# TB6612-4.net
KiCad netlist of a schematic drawn in EasyEDA Pro
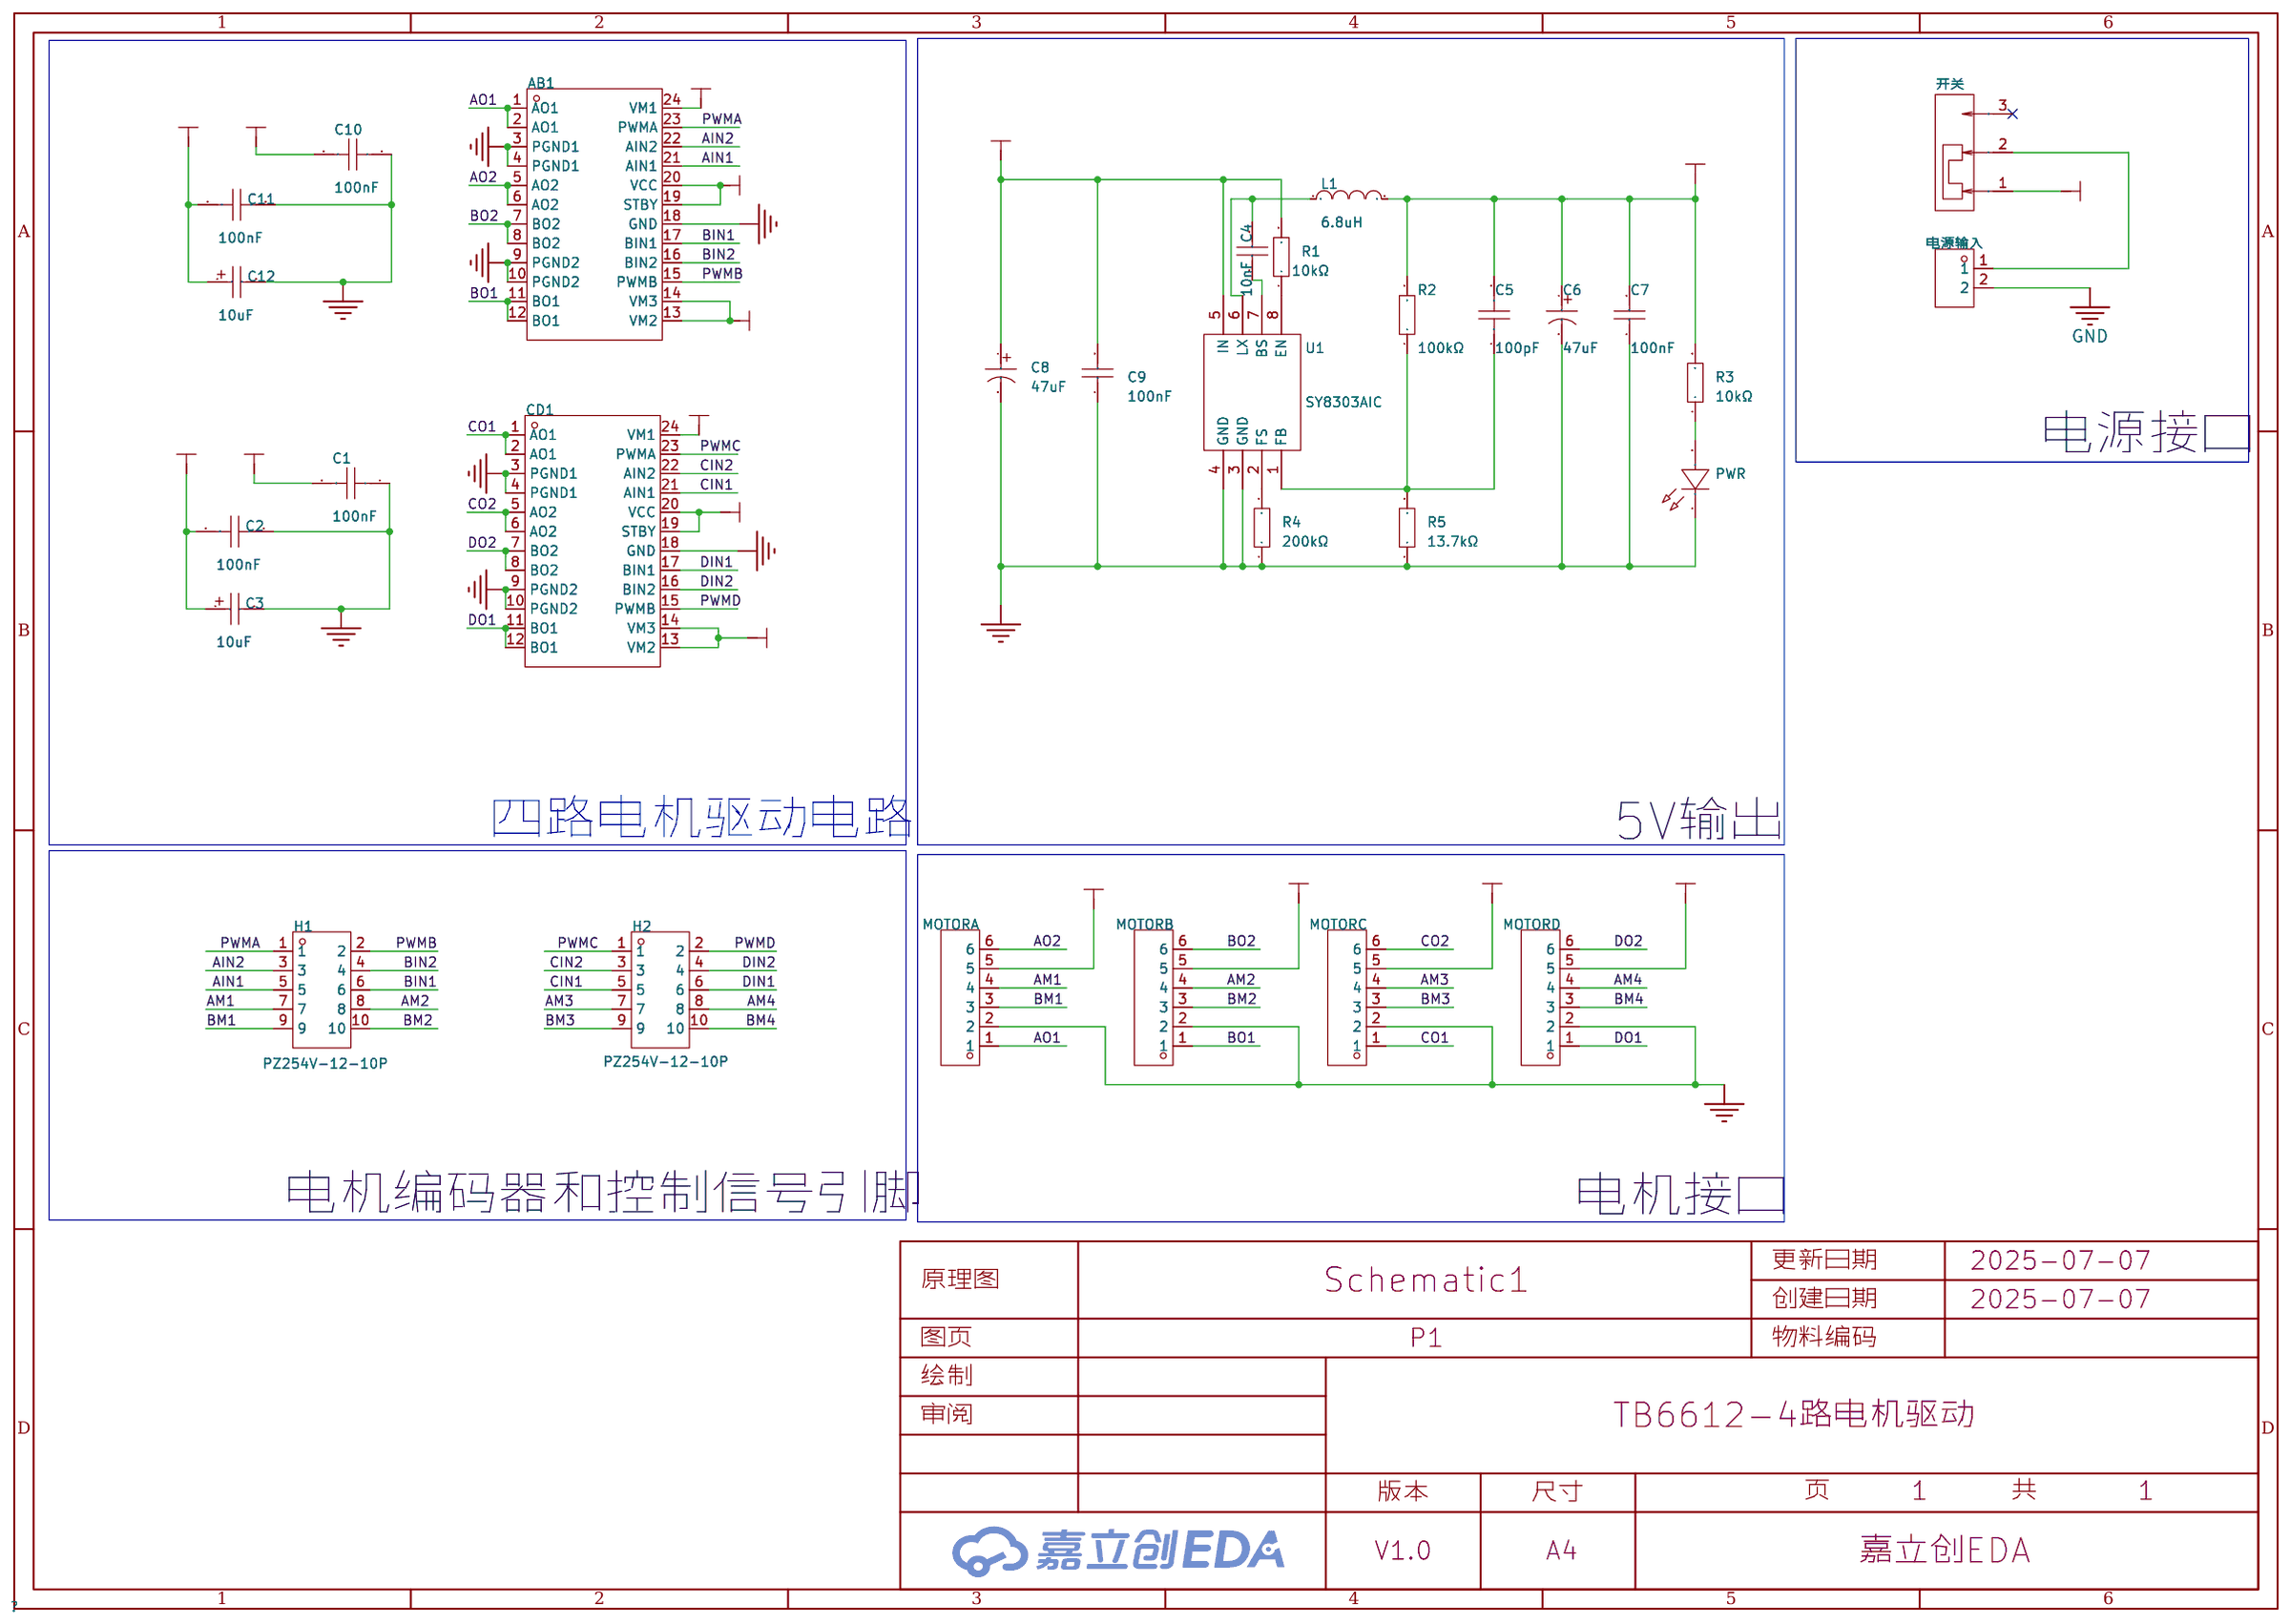
[diagram p0: schematic sheet]

(export (version "E")
  (design (tool "Eeschema 10.0.6"))
  (components
    (comp (ref "AB1")
      (value "TB6612FNG(O,C,8,EL")
      (footprint "easyedapro:SSOP-24_L8.4-W5.8-P0.65-LS7.8-BL")
      (description "双直流电机驱动器集成电路")
      (fields (field (name "Manufacturer") "TOSHIBA(东芝)"))
      (libsource (lib "easyedapro") (part "TB6612FNG(O,C,8,EL"))
    )
    (comp (ref "C1")
      (value "100nF")
      (footprint "easyedapro:C0603")
      (description "容值:100nF;精度:±10%;额定电压:50V;材质(温度系数):X7R;")
      (fields
        (field (name "Manufacturer Part") "CL10B104KB8NNNC")
        (field (name "Manufacturer") "SAMSUNG(三星)")
      )
      (libsource (lib "easyedapro") (part "CL10B104KB8NNNC"))
    )
    (comp (ref "C2")
      (value "100nF")
      (footprint "easyedapro:C0603")
      (description "容值:100nF;精度:±10%;额定电压:50V;材质(温度系数):X7R;")
      (fields
        (field (name "Manufacturer Part") "CL10B104KB8NNNC")
        (field (name "Manufacturer") "SAMSUNG(三星)")
      )
      (libsource (lib "easyedapro") (part "CL10B104KB8NNNC"))
    )
    (comp (ref "C3")
      (value "10uF")
      (footprint "easyedapro:CAP-SMD_L3.5-W2.8-R-RD")
      (description "容值:10uF;精度:±10%;额定电压:25V;等效串联电阻:2.5Ω@100kHz;")
      (fields (field (name "Manufacturer Part") "TAJB106K025RNJ") (field (name "Manufacturer") "Kyocera AVX"))
      (libsource (lib "easyedapro") (part "TAJB106K025RNJ"))
    )
    (comp (ref "C4")
      (value "10nF")
      (footprint "easyedapro:C0603")
      (description "容值:10nF;精度:±10%;额定电压:50V;材质(温度系数):X7R;")
      (fields
        (field (name "Manufacturer Part") "CC0603KRX7R9BB103")
        (field (name "Manufacturer") "YAGEO(国巨)")
      )
      (libsource (lib "easyedapro") (part "CC0603KRX7R9BB103"))
    )
    (comp (ref "C5")
      (value "100pF")
      (footprint "easyedapro:C0603")
      (description "容值:100pF;精度:±5%;额定电压:50V;材质(温度系数):NP0;")
      (fields
        (field (name "Manufacturer Part") "CC0603JRNPO9BN101")
        (field (name "Manufacturer") "YAGEO(国巨)")
      )
      (libsource (lib "easyedapro") (part "CC0603JRNPO9BN101"))
    )
    (comp (ref "C6")
      (value "47uF")
      (footprint "easyedapro:CAP-SMD_BD6.3-L6.6-W6.6-LS7.6-FD")
      (description "容值:47uF;精度:±20%;额定电压:50V;纹波电流:66mA@120Hz;等效串联电阻:-;")
      (fields (field (name "Manufacturer Part") "RVT1H470M0607") (field (name "Manufacturer") "ROQANG(容强)"))
      (libsource (lib "easyedapro") (part "RVT1H470M0607"))
    )
    (comp (ref "C7")
      (value "100nF")
      (footprint "easyedapro:C0603")
      (description "容值:100nF;精度:±10%;额定电压:50V;材质(温度系数):X7R;")
      (fields (field (name "Manufacturer Part") "0603B104K500NT") (field (name "Manufacturer") "FH(风华)"))
      (libsource (lib "easyedapro") (part "0603B104K500NT"))
    )
    (comp (ref "C8")
      (value "47uF")
      (footprint "easyedapro:CAP-SMD_BD6.3-L6.6-W6.6-LS7.6-FD")
      (description "容值:47uF;精度:±20%;额定电压:50V;纹波电流:66mA@120Hz;等效串联电阻:-;")
      (fields (field (name "Manufacturer Part") "RVT1H470M0607") (field (name "Manufacturer") "ROQANG(容强)"))
      (libsource (lib "easyedapro") (part "RVT1H470M0607"))
    )
    (comp (ref "C9")
      (value "100nF")
      (footprint "easyedapro:C0603")
      (description "容值:100nF;精度:±10%;额定电压:50V;材质(温度系数):X7R;")
      (fields (field (name "Manufacturer Part") "0603B104K500NT") (field (name "Manufacturer") "FH(风华)"))
      (libsource (lib "easyedapro") (part "0603B104K500NT"))
    )
    (comp (ref "C10")
      (value "100nF")
      (footprint "easyedapro:C0603")
      (description "容值:100nF;精度:±10%;额定电压:50V;材质(温度系数):X7R;")
      (fields
        (field (name "Manufacturer Part") "CL10B104KB8NNNC")
        (field (name "Manufacturer") "SAMSUNG(三星)")
      )
      (libsource (lib "easyedapro") (part "CL10B104KB8NNNC"))
    )
    (comp (ref "C11")
      (value "100nF")
      (footprint "easyedapro:C0603")
      (description "容值:100nF;精度:±10%;额定电压:50V;材质(温度系数):X7R;")
      (fields
        (field (name "Manufacturer Part") "CL10B104KB8NNNC")
        (field (name "Manufacturer") "SAMSUNG(三星)")
      )
      (libsource (lib "easyedapro") (part "CL10B104KB8NNNC"))
    )
    (comp (ref "C12")
      (value "10uF")
      (footprint "easyedapro:CAP-SMD_L3.5-W2.8-R-RD")
      (description "容值:10uF;精度:±10%;额定电压:25V;等效串联电阻:2.5Ω@100kHz;")
      (fields (field (name "Manufacturer Part") "TAJB106K025RNJ") (field (name "Manufacturer") "Kyocera AVX"))
      (libsource (lib "easyedapro") (part "TAJB106K025RNJ"))
    )
    (comp (ref "CD1")
      (value "TB6612FNG(O,C,8,EL")
      (footprint "easyedapro:SSOP-24_L8.4-W5.8-P0.65-LS7.8-BL")
      (description "双直流电机驱动器集成电路")
      (fields (field (name "Manufacturer") "TOSHIBA(东芝)"))
      (libsource (lib "easyedapro") (part "TB6612FNG(O,C,8,EL"))
    )
    (comp (ref "H1")
      (value "PZ254V-12-10P")
      (footprint "easyedapro:HDR-TH_10P-P2.54-V-M-R2-C5-S2.54")
      (fields (field (name "Manufacturer") "XFCN(兴飞)"))
      (libsource (lib "easyedapro") (part "PZ254V-12-10P"))
    )
    (comp (ref "H2")
      (value "PZ254V-12-10P")
      (footprint "easyedapro:HDR-TH_10P-P2.54-V-M-R2-C5-S2.54")
      (fields (field (name "Manufacturer") "XFCN(兴飞)"))
      (libsource (lib "easyedapro") (part "PZ254V-12-10P"))
    )
    (comp (ref "L1")
      (value "6.8uH")
      (footprint "easyedapro:IND-SMD_L4.4-W4.2")
      (description "电感值:6.8uH;精度:±20%;额定电流:2.4A;饱和电流(Isat):2.5A;类型:一体成型电感;")
      (fields (field (name "Manufacturer Part") "FXL0420-6R8-M") (field (name "Manufacturer") "cjiang(长江微电)"))
      (libsource (lib "easyedapro") (part "FXL0420-6R8-M"))
    )
    (comp (ref "MOTORA")
      (value "X8821WR-06S-N0SN")
      (footprint "easyedapro:CONN-TH_6P-P2.50_X8821WR-06S-N2SN")
      (description "插针结构:1x6P;间距:2.5mm;安装方式:弯插;参考系列:XH;总PIN数:6P;排数:1;每排PIN数:6;行距:-;额定电流:3A;触头材质:黄铜;触头镀层:锡;工作温度范围:-;")
      (fields (field (name "Manufacturer") "XKB Connection(中国星坤)"))
      (libsource (lib "easyedapro") (part "X8821WR-06S-N0SN"))
    )
    (comp (ref "MOTORB")
      (value "X8821WR-06S-N0SN")
      (footprint "easyedapro:CONN-TH_6P-P2.50_X8821WR-06S-N2SN")
      (description "插针结构:1x6P;间距:2.5mm;安装方式:弯插;参考系列:XH;总PIN数:6P;排数:1;每排PIN数:6;行距:-;额定电流:3A;触头材质:黄铜;触头镀层:锡;工作温度范围:-;")
      (fields (field (name "Manufacturer") "XKB Connection(中国星坤)"))
      (libsource (lib "easyedapro") (part "X8821WR-06S-N0SN"))
    )
    (comp (ref "MOTORC")
      (value "X8821WR-06S-N0SN")
      (footprint "easyedapro:CONN-TH_6P-P2.50_X8821WR-06S-N2SN")
      (description "插针结构:1x6P;间距:2.5mm;安装方式:弯插;参考系列:XH;总PIN数:6P;排数:1;每排PIN数:6;行距:-;额定电流:3A;触头材质:黄铜;触头镀层:锡;工作温度范围:-;")
      (fields (field (name "Manufacturer") "XKB Connection(中国星坤)"))
      (libsource (lib "easyedapro") (part "X8821WR-06S-N0SN"))
    )
    (comp (ref "MOTORD")
      (value "X8821WR-06S-N0SN")
      (footprint "easyedapro:CONN-TH_6P-P2.50_X8821WR-06S-N2SN")
      (description "插针结构:1x6P;间距:2.5mm;安装方式:弯插;参考系列:XH;总PIN数:6P;排数:1;每排PIN数:6;行距:-;额定电流:3A;触头材质:黄铜;触头镀层:锡;工作温度范围:-;")
      (fields (field (name "Manufacturer") "XKB Connection(中国星坤)"))
      (libsource (lib "easyedapro") (part "X8821WR-06S-N0SN"))
    )
    (comp (ref "PWR")
      (value "XL-1608UGC-04")
      (footprint "easyedapro:LED0603-RD_GREEN")
      (fields (field (name "Manufacturer") "XINGLIGHT(成兴光)"))
      (libsource (lib "easyedapro") (part "XL-1608UGC-04"))
    )
    (comp (ref "R1")
      (value "10kΩ")
      (footprint "easyedapro:R0603")
      (description "电阻类型:厚膜电阻;阻值:10kΩ;精度:±1%;功率:100mW;最大工作电压:75V;温度系数:±100ppm/°C;")
      (fields
        (field (name "Manufacturer Part") "0603WAF1002T5E")
        (field (name "Manufacturer") "UNI-ROYAL(厚声)")
      )
      (libsource (lib "easyedapro") (part "0603WAF1002T5E"))
    )
    (comp (ref "R2")
      (value "100kΩ")
      (footprint "easyedapro:R0603")
      (description "电阻类型:厚膜电阻;阻值:100kΩ;精度:±1%;功率:100mW;最大工作电压:75V;温度系数:±100ppm/°C;")
      (fields
        (field (name "Manufacturer Part") "0603WAF1003T5E")
        (field (name "Manufacturer") "UNI-ROYAL(厚声)")
      )
      (libsource (lib "easyedapro") (part "0603WAF1003T5E"))
    )
    (comp (ref "R3")
      (value "10kΩ")
      (footprint "easyedapro:R0603")
      (description "电阻类型:厚膜电阻;阻值:10kΩ;精度:±1%;功率:100mW;最大工作电压:75V;温度系数:±100ppm/°C;")
      (fields
        (field (name "Manufacturer Part") "0603WAF1002T5E")
        (field (name "Manufacturer") "UNI-ROYAL(厚声)")
      )
      (libsource (lib "easyedapro") (part "0603WAF1002T5E"))
    )
    (comp (ref "R4")
      (value "200kΩ")
      (footprint "easyedapro:R0603")
      (description "电阻类型:厚膜电阻;阻值:200kΩ;精度:±1%;功率:100mW;最大工作电压:75V;温度系数:±100ppm/°C;")
      (fields
        (field (name "Manufacturer Part") "0603WAF2003T5E")
        (field (name "Manufacturer") "UNI-ROYAL(厚声)")
      )
      (libsource (lib "easyedapro") (part "0603WAF2003T5E"))
    )
    (comp (ref "R5")
      (value "13.7kΩ")
      (footprint "easyedapro:R0603")
      (description "电阻类型:厚膜电阻;阻值:13.7kΩ;精度:±1%;功率:100mW;最大工作电压:75V;温度系数:±100ppm/°C;")
      (fields
        (field (name "Manufacturer Part") "0603WAF1372T5E")
        (field (name "Manufacturer") "UNI-ROYAL(厚声)")
      )
      (libsource (lib "easyedapro") (part "0603WAF1372T5E"))
    )
    (comp (ref "U1")
      (value "SY8303AIC")
      (footprint "easyedapro:TSOT-23-8_L2.9-W1.6-P0.65-LS2.8-BR")
      (description "功能类型:降压型;输入电压:-;输出电流(最大值):-;")
      (fields (field (name "Manufacturer") "silergy(矽力杰)"))
      (libsource (lib "easyedapro") (part "SY8303AIC"))
    )
    (comp (ref "开关")
      (value "SS-12D10-G5")
      (footprint "easyedapro:SW-TH_SS-12D10-G050")
      (description "电路结构:单刀双掷;安装方式:直插;开关颜色:黑色;滑钮形状:矩形柱状;引脚样式:PC引脚;开关长度:12.7mm;开关宽度:6.7mm;开关高度:11.3mm;")
      (fields (field (name "Manufacturer") "DEALON(德艺隆)"))
      (libsource (lib "easyedapro") (part "SS-12D10-G5"))
    )
    (comp (ref "电源输入")
      (value "KF301-5.0-2P")
      (footprint "easyedapro:CONN-TH_P5.00_KF301-5.0-2P")
      (fields (field (name "Manufacturer") "KEFA(科发)"))
      (libsource (lib "easyedapro") (part "KF301-5.0-2P"))
    )
  )
  (nets
    (net (code "1") (name "/AIN1") (class "Default")
      (node (ref "AB1") (pin "21") (pinfunction "AIN1_21") (pintype "unspecified"))
      (node (ref "H1") (pin "5") (pinfunction "5_5") (pintype "unspecified"))
    )
    (net (code "2") (name "/AIN2") (class "Default")
      (node (ref "AB1") (pin "22") (pinfunction "AIN2_22") (pintype "unspecified"))
      (node (ref "H1") (pin "3") (pinfunction "3_3") (pintype "unspecified"))
    )
    (net (code "3") (name "/AM1") (class "Default")
      (node (ref "H1") (pin "7") (pinfunction "7_7") (pintype "unspecified"))
      (node (ref "MOTORA") (pin "4") (pinfunction "4_4") (pintype "unspecified"))
    )
    (net (code "4") (name "/AM2") (class "Default")
      (node (ref "H1") (pin "8") (pinfunction "8_8") (pintype "unspecified"))
      (node (ref "MOTORB") (pin "4") (pinfunction "4_4") (pintype "unspecified"))
    )
    (net (code "5") (name "/AM3") (class "Default")
      (node (ref "H2") (pin "7") (pinfunction "7_7") (pintype "unspecified"))
      (node (ref "MOTORC") (pin "4") (pinfunction "4_4") (pintype "unspecified"))
    )
    (net (code "6") (name "/AM4") (class "Default")
      (node (ref "H2") (pin "8") (pinfunction "8_8") (pintype "unspecified"))
      (node (ref "MOTORD") (pin "4") (pinfunction "4_4") (pintype "unspecified"))
    )
    (net (code "7") (name "/AO1") (class "Default")
      (node (ref "AB1") (pin "1") (pinfunction "AO1_1") (pintype "unspecified"))
      (node (ref "AB1") (pin "2") (pinfunction "AO1_2") (pintype "unspecified"))
      (node (ref "MOTORA") (pin "1") (pinfunction "1_1") (pintype "unspecified"))
    )
    (net (code "8") (name "/AO2") (class "Default")
      (node (ref "AB1") (pin "5") (pinfunction "AO2_5") (pintype "unspecified"))
      (node (ref "AB1") (pin "6") (pinfunction "AO2_6") (pintype "unspecified"))
      (node (ref "MOTORA") (pin "6") (pinfunction "6_6") (pintype "unspecified"))
    )
    (net (code "9") (name "/BIN1") (class "Default")
      (node (ref "AB1") (pin "17") (pinfunction "BIN1_17") (pintype "unspecified"))
      (node (ref "H1") (pin "6") (pinfunction "6_6") (pintype "unspecified"))
    )
    (net (code "10") (name "/BIN2") (class "Default")
      (node (ref "AB1") (pin "16") (pinfunction "BIN2_16") (pintype "unspecified"))
      (node (ref "H1") (pin "4") (pinfunction "4_4") (pintype "unspecified"))
    )
    (net (code "11") (name "/BM1") (class "Default")
      (node (ref "H1") (pin "9") (pinfunction "9_9") (pintype "unspecified"))
      (node (ref "MOTORA") (pin "3") (pinfunction "3_3") (pintype "unspecified"))
    )
    (net (code "12") (name "/BM2") (class "Default")
      (node (ref "H1") (pin "10") (pinfunction "10_10") (pintype "unspecified"))
      (node (ref "MOTORB") (pin "3") (pinfunction "3_3") (pintype "unspecified"))
    )
    (net (code "13") (name "/BM3") (class "Default")
      (node (ref "H2") (pin "9") (pinfunction "9_9") (pintype "unspecified"))
      (node (ref "MOTORC") (pin "3") (pinfunction "3_3") (pintype "unspecified"))
    )
    (net (code "14") (name "/BM4") (class "Default")
      (node (ref "H2") (pin "10") (pinfunction "10_10") (pintype "unspecified"))
      (node (ref "MOTORD") (pin "3") (pinfunction "3_3") (pintype "unspecified"))
    )
    (net (code "15") (name "/BO1") (class "Default")
      (node (ref "AB1") (pin "11") (pinfunction "BO1_11") (pintype "unspecified"))
      (node (ref "AB1") (pin "12") (pinfunction "BO1_12") (pintype "unspecified"))
      (node (ref "MOTORB") (pin "1") (pinfunction "1_1") (pintype "unspecified"))
    )
    (net (code "16") (name "/BO2") (class "Default")
      (node (ref "AB1") (pin "7") (pinfunction "BO2_7") (pintype "unspecified"))
      (node (ref "AB1") (pin "8") (pinfunction "BO2_8") (pintype "unspecified"))
      (node (ref "MOTORB") (pin "6") (pinfunction "6_6") (pintype "unspecified"))
    )
    (net (code "17") (name "/CIN1") (class "Default")
      (node (ref "CD1") (pin "21") (pinfunction "AIN1_21") (pintype "unspecified"))
      (node (ref "H2") (pin "5") (pinfunction "5_5") (pintype "unspecified"))
    )
    (net (code "18") (name "/CIN2") (class "Default")
      (node (ref "CD1") (pin "22") (pinfunction "AIN2_22") (pintype "unspecified"))
      (node (ref "H2") (pin "3") (pinfunction "3_3") (pintype "unspecified"))
    )
    (net (code "19") (name "/CO1") (class "Default")
      (node (ref "CD1") (pin "1") (pinfunction "AO1_1") (pintype "unspecified"))
      (node (ref "CD1") (pin "2") (pinfunction "AO1_2") (pintype "unspecified"))
      (node (ref "MOTORC") (pin "1") (pinfunction "1_1") (pintype "unspecified"))
    )
    (net (code "20") (name "/CO2") (class "Default")
      (node (ref "CD1") (pin "5") (pinfunction "AO2_5") (pintype "unspecified"))
      (node (ref "CD1") (pin "6") (pinfunction "AO2_6") (pintype "unspecified"))
      (node (ref "MOTORC") (pin "6") (pinfunction "6_6") (pintype "unspecified"))
    )
    (net (code "21") (name "/DIN1") (class "Default")
      (node (ref "CD1") (pin "17") (pinfunction "BIN1_17") (pintype "unspecified"))
      (node (ref "H2") (pin "6") (pinfunction "6_6") (pintype "unspecified"))
    )
    (net (code "22") (name "/DIN2") (class "Default")
      (node (ref "CD1") (pin "16") (pinfunction "BIN2_16") (pintype "unspecified"))
      (node (ref "H2") (pin "4") (pinfunction "4_4") (pintype "unspecified"))
    )
    (net (code "23") (name "/DO1") (class "Default")
      (node (ref "CD1") (pin "11") (pinfunction "BO1_11") (pintype "unspecified"))
      (node (ref "CD1") (pin "12") (pinfunction "BO1_12") (pintype "unspecified"))
      (node (ref "MOTORD") (pin "1") (pinfunction "1_1") (pintype "unspecified"))
    )
    (net (code "24") (name "/DO2") (class "Default")
      (node (ref "CD1") (pin "7") (pinfunction "BO2_7") (pintype "unspecified"))
      (node (ref "CD1") (pin "8") (pinfunction "BO2_8") (pintype "unspecified"))
      (node (ref "MOTORD") (pin "6") (pinfunction "6_6") (pintype "unspecified"))
    )
    (net (code "25") (name "/PWMA") (class "Default")
      (node (ref "AB1") (pin "23") (pinfunction "PWMA_23") (pintype "unspecified"))
      (node (ref "H1") (pin "1") (pinfunction "1_1") (pintype "unspecified"))
    )
    (net (code "26") (name "/PWMB") (class "Default")
      (node (ref "AB1") (pin "15") (pinfunction "PWMB_15") (pintype "unspecified"))
      (node (ref "H1") (pin "2") (pinfunction "2_2") (pintype "unspecified"))
    )
    (net (code "27") (name "/PWMC") (class "Default")
      (node (ref "CD1") (pin "23") (pinfunction "PWMA_23") (pintype "unspecified"))
      (node (ref "H2") (pin "1") (pinfunction "1_1") (pintype "unspecified"))
    )
    (net (code "28") (name "/PWMD") (class "Default")
      (node (ref "CD1") (pin "15") (pinfunction "PWMB_15") (pintype "unspecified"))
      (node (ref "H2") (pin "2") (pinfunction "2_2") (pintype "unspecified"))
    )
    (net (code "29") (name "5V") (class "Default")
      (node (ref "AB1") (pin "19") (pinfunction "STBY_19") (pintype "unspecified"))
      (node (ref "AB1") (pin "20") (pinfunction "VCC_20") (pintype "unspecified"))
      (node (ref "C1") (pin "2") (pinfunction "2_2") (pintype "unspecified"))
      (node (ref "C10") (pin "2") (pinfunction "2_2") (pintype "unspecified"))
      (node (ref "C5") (pin "2") (pinfunction "2_2") (pintype "unspecified"))
      (node (ref "C6") (pin "1") (pinfunction "1_1") (pintype "input"))
      (node (ref "C7") (pin "2") (pinfunction "2_2") (pintype "input"))
      (node (ref "CD1") (pin "19") (pinfunction "STBY_19") (pintype "unspecified"))
      (node (ref "CD1") (pin "20") (pinfunction "VCC_20") (pintype "unspecified"))
      (node (ref "L1") (pin "2") (pinfunction "2_2") (pintype "unspecified"))
      (node (ref "MOTORA") (pin "5") (pinfunction "5_5") (pintype "unspecified"))
      (node (ref "MOTORB") (pin "5") (pinfunction "5_5") (pintype "unspecified"))
      (node (ref "MOTORC") (pin "5") (pinfunction "5_5") (pintype "unspecified"))
      (node (ref "MOTORD") (pin "5") (pinfunction "5_5") (pintype "unspecified"))
      (node (ref "R2") (pin "2") (pinfunction "2_2") (pintype "input"))
      (node (ref "R3") (pin "2") (pinfunction "2_2") (pintype "input"))
    )
    (net (code "30") (name "12V") (class "Default")
      (node (ref "AB1") (pin "13") (pinfunction "VM2_13") (pintype "unspecified"))
      (node (ref "AB1") (pin "14") (pinfunction "VM3_14") (pintype "unspecified"))
      (node (ref "AB1") (pin "24") (pinfunction "VM1_24") (pintype "unspecified"))
      (node (ref "C11") (pin "2") (pinfunction "2_2") (pintype "unspecified"))
      (node (ref "C12") (pin "1") (pinfunction "1_1") (pintype "input"))
      (node (ref "C2") (pin "2") (pinfunction "2_2") (pintype "unspecified"))
      (node (ref "C3") (pin "1") (pinfunction "1_1") (pintype "input"))
      (node (ref "C8") (pin "1") (pinfunction "1_1") (pintype "input"))
      (node (ref "C9") (pin "2") (pinfunction "2_2") (pintype "input"))
      (node (ref "CD1") (pin "13") (pinfunction "VM2_13") (pintype "unspecified"))
      (node (ref "CD1") (pin "14") (pinfunction "VM3_14") (pintype "unspecified"))
      (node (ref "CD1") (pin "24") (pinfunction "VM1_24") (pintype "unspecified"))
      (node (ref "R1") (pin "2") (pinfunction "2_2") (pintype "input"))
      (node (ref "U1") (pin "5") (pinfunction "IN_5") (pintype "input"))
      (node (ref "开关") (pin "1") (pinfunction "1_1") (pintype "input"))
    )
    (net (code "31") (name "GND") (class "Default")
      (node (ref "AB1") (pin "10") (pinfunction "PGND2_10") (pintype "unspecified"))
      (node (ref "AB1") (pin "18") (pinfunction "GND_18") (pintype "unspecified"))
      (node (ref "AB1") (pin "3") (pinfunction "PGND1_3") (pintype "unspecified"))
      (node (ref "AB1") (pin "4") (pinfunction "PGND1_4") (pintype "unspecified"))
      (node (ref "AB1") (pin "9") (pinfunction "PGND2_9") (pintype "unspecified"))
      (node (ref "C1") (pin "1") (pinfunction "1_1") (pintype "unspecified"))
      (node (ref "C10") (pin "1") (pinfunction "1_1") (pintype "unspecified"))
      (node (ref "C11") (pin "1") (pinfunction "1_1") (pintype "unspecified"))
      (node (ref "C12") (pin "2") (pinfunction "2_2") (pintype "input"))
      (node (ref "C2") (pin "1") (pinfunction "1_1") (pintype "unspecified"))
      (node (ref "C3") (pin "2") (pinfunction "2_2") (pintype "input"))
      (node (ref "C6") (pin "2") (pinfunction "2_2") (pintype "input"))
      (node (ref "C7") (pin "1") (pinfunction "1_1") (pintype "input"))
      (node (ref "C8") (pin "2") (pinfunction "2_2") (pintype "input"))
      (node (ref "C9") (pin "1") (pinfunction "1_1") (pintype "input"))
      (node (ref "CD1") (pin "10") (pinfunction "PGND2_10") (pintype "unspecified"))
      (node (ref "CD1") (pin "18") (pinfunction "GND_18") (pintype "unspecified"))
      (node (ref "CD1") (pin "3") (pinfunction "PGND1_3") (pintype "unspecified"))
      (node (ref "CD1") (pin "4") (pinfunction "PGND1_4") (pintype "unspecified"))
      (node (ref "CD1") (pin "9") (pinfunction "PGND2_9") (pintype "unspecified"))
      (node (ref "MOTORA") (pin "2") (pinfunction "2_2") (pintype "unspecified"))
      (node (ref "MOTORB") (pin "2") (pinfunction "2_2") (pintype "unspecified"))
      (node (ref "MOTORC") (pin "2") (pinfunction "2_2") (pintype "unspecified"))
      (node (ref "MOTORD") (pin "2") (pinfunction "2_2") (pintype "unspecified"))
      (node (ref "PWR") (pin "1") (pinfunction "K_1") (pintype "unspecified"))
      (node (ref "R4") (pin "1") (pinfunction "1_1") (pintype "input"))
      (node (ref "R5") (pin "1") (pinfunction "1_1") (pintype "input"))
      (node (ref "U1") (pin "3") (pinfunction "GND_3") (pintype "input"))
      (node (ref "U1") (pin "4") (pinfunction "GND_4") (pintype "input"))
      (node (ref "电源输入") (pin "2") (pinfunction "2_2") (pintype "unspecified"))
    )
    (net (code "32") (name "Net-(PWR-A)") (class "Default")
      (node (ref "PWR") (pin "2") (pinfunction "A_2") (pintype "unspecified"))
      (node (ref "R3") (pin "1") (pinfunction "1_1") (pintype "input"))
    )
    (net (code "33") (name "Net-(U1-BS)") (class "Default")
      (node (ref "C4") (pin "1") (pinfunction "1_1") (pintype "input"))
      (node (ref "U1") (pin "7") (pinfunction "BS_7") (pintype "input"))
    )
    (net (code "34") (name "Net-(U1-EN)") (class "Default")
      (node (ref "R1") (pin "1") (pinfunction "1_1") (pintype "input"))
      (node (ref "U1") (pin "8") (pinfunction "EN_8") (pintype "input"))
    )
    (net (code "35") (name "Net-(U1-FB)") (class "Default")
      (node (ref "C5") (pin "1") (pinfunction "1_1") (pintype "unspecified"))
      (node (ref "R2") (pin "1") (pinfunction "1_1") (pintype "input"))
      (node (ref "R5") (pin "2") (pinfunction "2_2") (pintype "input"))
      (node (ref "U1") (pin "1") (pinfunction "FB_1") (pintype "input"))
    )
    (net (code "36") (name "Net-(U1-FS)") (class "Default")
      (node (ref "R4") (pin "2") (pinfunction "2_2") (pintype "input"))
      (node (ref "U1") (pin "2") (pinfunction "FS_2") (pintype "input"))
    )
    (net (code "37") (name "Net-(U1-LX)") (class "Default")
      (node (ref "C4") (pin "2") (pinfunction "2_2") (pintype "input"))
      (node (ref "L1") (pin "1") (pinfunction "1_1") (pintype "unspecified"))
      (node (ref "U1") (pin "6") (pinfunction "LX_6") (pintype "input"))
    )
    (net (code "38") (name "Net-(开关-Pad2)") (class "Default")
      (node (ref "开关") (pin "2") (pinfunction "2_2") (pintype "input"))
      (node (ref "电源输入") (pin "1") (pinfunction "1_1") (pintype "unspecified"))
    )
    (net (code "39") (name "unconnected-(开关-Pad3)") (class "Default")
      (node (ref "开关") (pin "3") (pinfunction "3_3") (pintype "input+no_connect"))
    )
  )
)
